# TestPowerMergeSys.net
KiCad netlist of a schematic drawn in Altium Designer
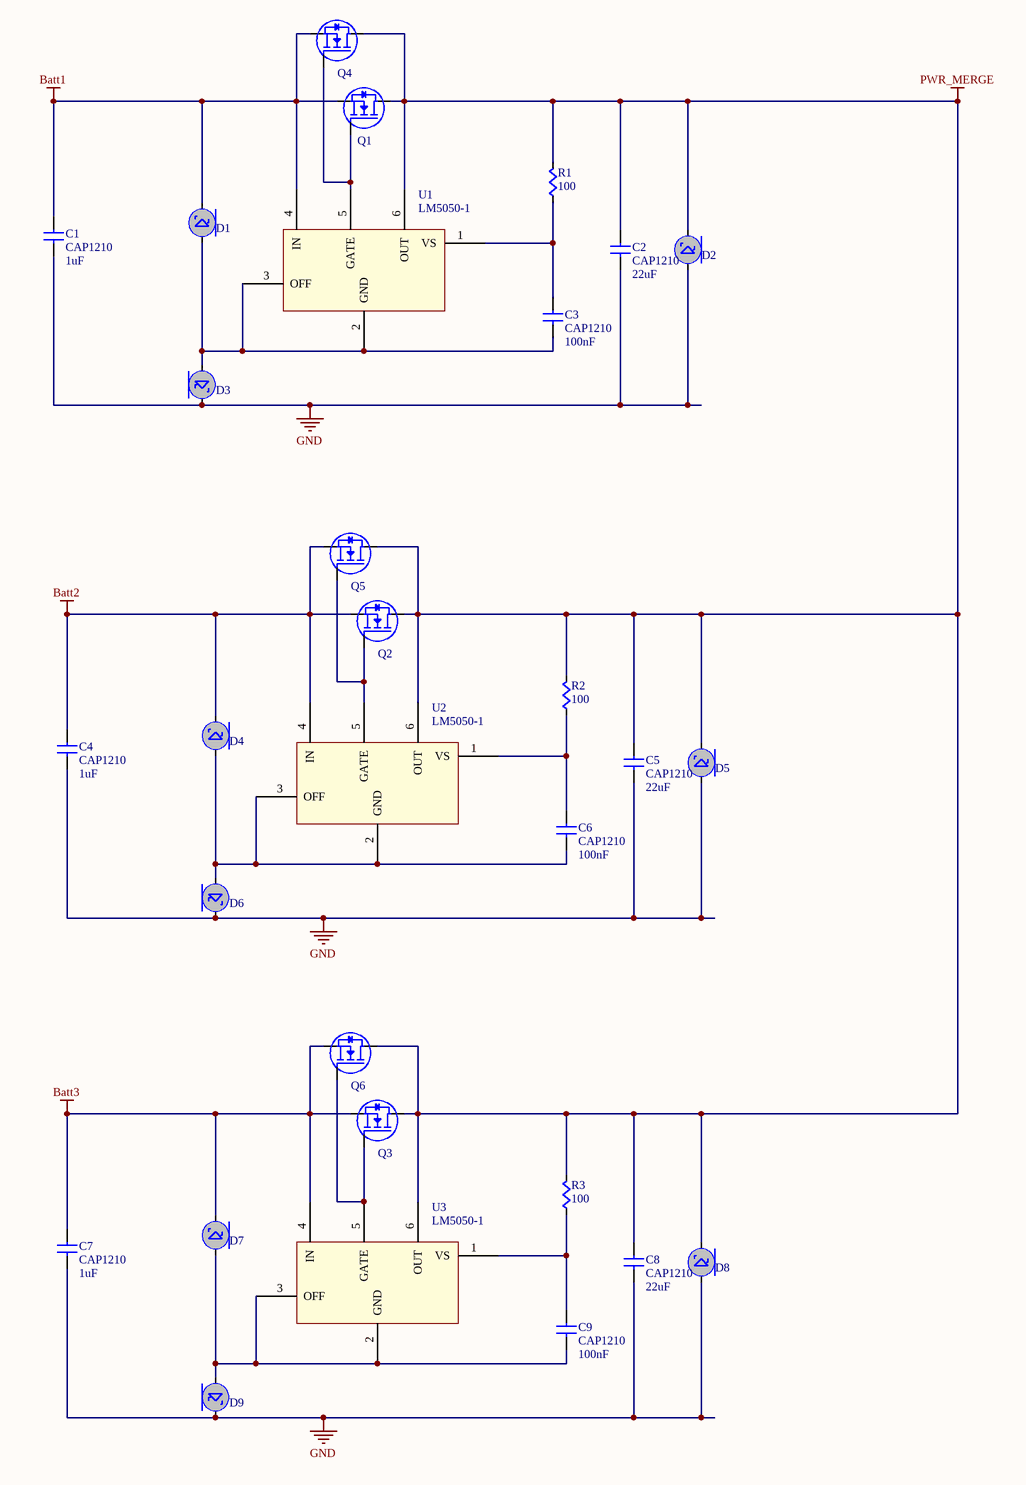
[diagram p0: TestPowerMergeSys.SchDoc]

(export (version "E")
  (design (tool "Eeschema 10.0.6"))
  (components
    (comp (ref "C1")
      (value "CAP1210")
      (footprint "CAP1210")
      (description "CAP CER 10UF 50V 20% X5R 1210")
      (fields (field (name "ALTIUM_VALUE") "1uF"))
      (libsource (lib "SubjuGator8") (part "CAP1210"))
    )
    (comp (ref "C2")
      (value "CAP1210")
      (footprint "CAP1210")
      (description "CAP CER 10UF 50V 20% X5R 1210")
      (fields (field (name "ALTIUM_VALUE") "22uF"))
      (libsource (lib "SubjuGator8") (part "CAP1210"))
    )
    (comp (ref "C3")
      (value "CAP1210")
      (footprint "CAP1210")
      (description "CAP CER 10UF 50V 20% X5R 1210")
      (fields (field (name "ALTIUM_VALUE") "100nF"))
      (libsource (lib "SubjuGator8") (part "CAP1210"))
    )
    (comp (ref "C4")
      (value "CAP1210")
      (footprint "CAP1210")
      (description "CAP CER 10UF 50V 20% X5R 1210")
      (fields (field (name "ALTIUM_VALUE") "1uF"))
      (libsource (lib "SubjuGator8") (part "CAP1210"))
    )
    (comp (ref "C5")
      (value "CAP1210")
      (footprint "CAP1210")
      (description "CAP CER 10UF 50V 20% X5R 1210")
      (fields (field (name "ALTIUM_VALUE") "22uF"))
      (libsource (lib "SubjuGator8") (part "CAP1210"))
    )
    (comp (ref "C6")
      (value "CAP1210")
      (footprint "CAP1210")
      (description "CAP CER 10UF 50V 20% X5R 1210")
      (fields (field (name "ALTIUM_VALUE") "100nF"))
      (libsource (lib "SubjuGator8") (part "CAP1210"))
    )
    (comp (ref "C7")
      (value "CAP1210")
      (footprint "CAP1210")
      (description "CAP CER 10UF 50V 20% X5R 1210")
      (fields (field (name "ALTIUM_VALUE") "1uF"))
      (libsource (lib "SubjuGator8") (part "CAP1210"))
    )
    (comp (ref "C8")
      (value "CAP1210")
      (footprint "CAP1210")
      (description "CAP CER 10UF 50V 20% X5R 1210")
      (fields (field (name "ALTIUM_VALUE") "22uF"))
      (libsource (lib "SubjuGator8") (part "CAP1210"))
    )
    (comp (ref "C9")
      (value "CAP1210")
      (footprint "CAP1210")
      (description "CAP CER 10UF 50V 20% X5R 1210")
      (fields (field (name "ALTIUM_VALUE") "100nF"))
      (libsource (lib "SubjuGator8") (part "CAP1210"))
    )
    (comp (ref "D1")
      (value "SS16T3G")
      (footprint "SS16T3G")
      (description "DIODE SCHOTTKY 60V 1A SMA")
      (libsource (lib "") (part "SS16T3G_1"))
    )
    (comp (ref "D2")
      (value "SMBJ60A-13-F")
      (footprint "SMBJ60A-13-F")
      (description "TVS UNIDIRECT 600W 60V SMB")
      (libsource (lib "SubjuGator8") (part "SMBJ60A-13-F"))
    )
    (comp (ref "D3")
      (value "SS16T3G")
      (footprint "SS16T3G")
      (description "DIODE SCHOTTKY 60V 1A SMA")
      (libsource (lib "SubjuGator8") (part "SS16T3G"))
    )
    (comp (ref "D4")
      (value "SS16T3G")
      (footprint "SS16T3G")
      (description "DIODE SCHOTTKY 60V 1A SMA")
      (libsource (lib "") (part "SS16T3G_1"))
    )
    (comp (ref "D5")
      (value "SMBJ60A-13-F")
      (footprint "SMBJ60A-13-F")
      (description "TVS UNIDIRECT 600W 60V SMB")
      (libsource (lib "SubjuGator8") (part "SMBJ60A-13-F"))
    )
    (comp (ref "D6")
      (value "SS16T3G")
      (footprint "SS16T3G")
      (description "DIODE SCHOTTKY 60V 1A SMA")
      (libsource (lib "SubjuGator8") (part "SS16T3G"))
    )
    (comp (ref "D7")
      (value "SS16T3G")
      (footprint "SS16T3G")
      (description "DIODE SCHOTTKY 60V 1A SMA")
      (libsource (lib "") (part "SS16T3G_1"))
    )
    (comp (ref "D8")
      (value "SMBJ60A-13-F")
      (footprint "SMBJ60A-13-F")
      (description "TVS UNIDIRECT 600W 60V SMB")
      (libsource (lib "SubjuGator8") (part "SMBJ60A-13-F"))
    )
    (comp (ref "D9")
      (value "SS16T3G")
      (footprint "SS16T3G")
      (description "DIODE SCHOTTKY 60V 1A SMA")
      (libsource (lib "SubjuGator8") (part "SS16T3G"))
    )
    (comp (ref "Q1")
      (value "IRFB3306PbF")
      (footprint "TO-220AB Heatsink")
      (description "HEXFET Power MOSFET")
      (libsource (lib "SubjuGator8") (part "IRFx3306PbF"))
    )
    (comp (ref "Q2")
      (value "IRFB3306PbF")
      (footprint "TO-220AB Heatsink")
      (description "HEXFET Power MOSFET")
      (libsource (lib "SubjuGator8") (part "IRFx3306PbF"))
    )
    (comp (ref "Q3")
      (value "IRFB3306PbF")
      (footprint "TO-220AB Heatsink")
      (description "HEXFET Power MOSFET")
      (libsource (lib "SubjuGator8") (part "IRFx3306PbF"))
    )
    (comp (ref "Q4")
      (value "IRFB3306PbF")
      (footprint "TO-220AB Heatsink")
      (description "HEXFET Power MOSFET")
      (libsource (lib "SubjuGator8") (part "IRFx3306PbF"))
    )
    (comp (ref "Q5")
      (value "IRFB3306PbF")
      (footprint "TO-220AB Heatsink")
      (description "HEXFET Power MOSFET")
      (libsource (lib "SubjuGator8") (part "IRFx3306PbF"))
    )
    (comp (ref "Q6")
      (value "IRFB3306PbF")
      (footprint "TO-220AB Heatsink")
      (description "HEXFET Power MOSFET")
      (libsource (lib "SubjuGator8") (part "IRFx3306PbF"))
    )
    (comp (ref "R1")
      (value "100")
      (footprint "RES0603")
      (fields (field (name "Comment") "Res"))
      (libsource (lib "SubjuGator8") (part "Res"))
    )
    (comp (ref "R2")
      (value "100")
      (footprint "RES0603")
      (fields (field (name "Comment") "Res"))
      (libsource (lib "SubjuGator8") (part "Res"))
    )
    (comp (ref "R3")
      (value "100")
      (footprint "RES0603")
      (fields (field (name "Comment") "Res"))
      (libsource (lib "SubjuGator8") (part "Res"))
    )
    (comp (ref "U1")
      (value "LM5050-1")
      (footprint "LM5050")
      (description "High-Side OR-ing FET Controller")
      (libsource (lib "SubjuGator8") (part "LM5050"))
    )
    (comp (ref "U2")
      (value "LM5050-1")
      (footprint "LM5050")
      (description "High-Side OR-ing FET Controller")
      (libsource (lib "SubjuGator8") (part "LM5050"))
    )
    (comp (ref "U3")
      (value "LM5050-1")
      (footprint "LM5050")
      (description "High-Side OR-ing FET Controller")
      (libsource (lib "SubjuGator8") (part "LM5050"))
    )
  )
  (nets
    (net (code "1") (name "Batt1") (class "Default")
      (node (ref "C1") (pin "1") (pinfunction "A_1") (pintype "passive"))
      (node (ref "D1") (pin "C") (pinfunction "C_C") (pintype "passive"))
      (node (ref "Q1") (pin "S") (pinfunction "S_S") (pintype "passive"))
      (node (ref "Q4") (pin "S") (pinfunction "S_S") (pintype "passive"))
      (node (ref "U1") (pin "4") (pinfunction "IN_4") (pintype "passive"))
    )
    (net (code "2") (name "Batt2") (class "Default")
      (node (ref "C4") (pin "1") (pinfunction "A_1") (pintype "passive"))
      (node (ref "D4") (pin "C") (pinfunction "C_C") (pintype "passive"))
      (node (ref "Q2") (pin "S") (pinfunction "S_S") (pintype "passive"))
      (node (ref "Q5") (pin "S") (pinfunction "S_S") (pintype "passive"))
      (node (ref "U2") (pin "4") (pinfunction "IN_4") (pintype "passive"))
    )
    (net (code "3") (name "Batt3") (class "Default")
      (node (ref "C7") (pin "1") (pinfunction "A_1") (pintype "passive"))
      (node (ref "D7") (pin "C") (pinfunction "C_C") (pintype "passive"))
      (node (ref "Q3") (pin "S") (pinfunction "S_S") (pintype "passive"))
      (node (ref "Q6") (pin "S") (pinfunction "S_S") (pintype "passive"))
      (node (ref "U3") (pin "4") (pinfunction "IN_4") (pintype "passive"))
    )
    (net (code "4") (name "GND") (class "Default")
      (node (ref "C1") (pin "2") (pinfunction "B_2") (pintype "passive"))
      (node (ref "C2") (pin "2") (pinfunction "B_2") (pintype "passive"))
      (node (ref "C4") (pin "2") (pinfunction "B_2") (pintype "passive"))
      (node (ref "C5") (pin "2") (pinfunction "B_2") (pintype "passive"))
      (node (ref "C7") (pin "2") (pinfunction "B_2") (pintype "passive"))
      (node (ref "C8") (pin "2") (pinfunction "B_2") (pintype "passive"))
      (node (ref "D2") (pin "A") (pinfunction "A_A") (pintype "passive"))
      (node (ref "D3") (pin "C") (pinfunction "C_C") (pintype "passive"))
      (node (ref "D5") (pin "A") (pinfunction "A_A") (pintype "passive"))
      (node (ref "D6") (pin "C") (pinfunction "C_C") (pintype "passive"))
      (node (ref "D8") (pin "A") (pinfunction "A_A") (pintype "passive"))
      (node (ref "D9") (pin "C") (pinfunction "C_C") (pintype "passive"))
    )
    (net (code "5") (name "Net-(C3-A)") (class "Default")
      (node (ref "C3") (pin "1") (pinfunction "A_1") (pintype "passive"))
      (node (ref "R1") (pin "2") (pinfunction "B_2") (pintype "passive"))
      (node (ref "U1") (pin "1") (pinfunction "VS_1") (pintype "passive"))
    )
    (net (code "6") (name "Net-(C3-B)") (class "Default")
      (node (ref "C3") (pin "2") (pinfunction "B_2") (pintype "passive"))
      (node (ref "D1") (pin "A") (pinfunction "A_A") (pintype "passive"))
      (node (ref "D3") (pin "A") (pinfunction "A_A") (pintype "passive"))
      (node (ref "U1") (pin "2") (pinfunction "GND_2") (pintype "passive"))
      (node (ref "U1") (pin "3") (pinfunction "OFF_3") (pintype "passive"))
    )
    (net (code "7") (name "Net-(C6-A)") (class "Default")
      (node (ref "C6") (pin "1") (pinfunction "A_1") (pintype "passive"))
      (node (ref "R2") (pin "2") (pinfunction "B_2") (pintype "passive"))
      (node (ref "U2") (pin "1") (pinfunction "VS_1") (pintype "passive"))
    )
    (net (code "8") (name "Net-(C6-B)") (class "Default")
      (node (ref "C6") (pin "2") (pinfunction "B_2") (pintype "passive"))
      (node (ref "D4") (pin "A") (pinfunction "A_A") (pintype "passive"))
      (node (ref "D6") (pin "A") (pinfunction "A_A") (pintype "passive"))
      (node (ref "U2") (pin "2") (pinfunction "GND_2") (pintype "passive"))
      (node (ref "U2") (pin "3") (pinfunction "OFF_3") (pintype "passive"))
    )
    (net (code "9") (name "Net-(C9-A)") (class "Default")
      (node (ref "C9") (pin "1") (pinfunction "A_1") (pintype "passive"))
      (node (ref "R3") (pin "2") (pinfunction "B_2") (pintype "passive"))
      (node (ref "U3") (pin "1") (pinfunction "VS_1") (pintype "passive"))
    )
    (net (code "10") (name "Net-(C9-B)") (class "Default")
      (node (ref "C9") (pin "2") (pinfunction "B_2") (pintype "passive"))
      (node (ref "D7") (pin "A") (pinfunction "A_A") (pintype "passive"))
      (node (ref "D9") (pin "A") (pinfunction "A_A") (pintype "passive"))
      (node (ref "U3") (pin "2") (pinfunction "GND_2") (pintype "passive"))
      (node (ref "U3") (pin "3") (pinfunction "OFF_3") (pintype "passive"))
    )
    (net (code "11") (name "Net-(U1-GATE)") (class "Default")
      (node (ref "Q1") (pin "G") (pinfunction "G_G") (pintype "passive"))
      (node (ref "Q4") (pin "G") (pinfunction "G_G") (pintype "passive"))
      (node (ref "U1") (pin "5") (pinfunction "GATE_5") (pintype "passive"))
    )
    (net (code "12") (name "Net-(U2-GATE)") (class "Default")
      (node (ref "Q2") (pin "G") (pinfunction "G_G") (pintype "passive"))
      (node (ref "Q5") (pin "G") (pinfunction "G_G") (pintype "passive"))
      (node (ref "U2") (pin "5") (pinfunction "GATE_5") (pintype "passive"))
    )
    (net (code "13") (name "Net-(U3-GATE)") (class "Default")
      (node (ref "Q3") (pin "G") (pinfunction "G_G") (pintype "passive"))
      (node (ref "Q6") (pin "G") (pinfunction "G_G") (pintype "passive"))
      (node (ref "U3") (pin "5") (pinfunction "GATE_5") (pintype "passive"))
    )
    (net (code "14") (name "PWR_MERGE") (class "Default")
      (node (ref "C2") (pin "1") (pinfunction "A_1") (pintype "passive"))
      (node (ref "C5") (pin "1") (pinfunction "A_1") (pintype "passive"))
      (node (ref "C8") (pin "1") (pinfunction "A_1") (pintype "passive"))
      (node (ref "D2") (pin "C") (pinfunction "C_C") (pintype "passive"))
      (node (ref "D5") (pin "C") (pinfunction "C_C") (pintype "passive"))
      (node (ref "D8") (pin "C") (pinfunction "C_C") (pintype "passive"))
      (node (ref "Q1") (pin "D") (pinfunction "D_D") (pintype "passive"))
      (node (ref "Q2") (pin "D") (pinfunction "D_D") (pintype "passive"))
      (node (ref "Q3") (pin "D") (pinfunction "D_D") (pintype "passive"))
      (node (ref "Q4") (pin "D") (pinfunction "D_D") (pintype "passive"))
      (node (ref "Q5") (pin "D") (pinfunction "D_D") (pintype "passive"))
      (node (ref "Q6") (pin "D") (pinfunction "D_D") (pintype "passive"))
      (node (ref "R1") (pin "1") (pinfunction "A_1") (pintype "passive"))
      (node (ref "R2") (pin "1") (pinfunction "A_1") (pintype "passive"))
      (node (ref "R3") (pin "1") (pinfunction "A_1") (pintype "passive"))
      (node (ref "U1") (pin "6") (pinfunction "OUT_6") (pintype "passive"))
      (node (ref "U2") (pin "6") (pinfunction "OUT_6") (pintype "passive"))
      (node (ref "U3") (pin "6") (pinfunction "OUT_6") (pintype "passive"))
    )
  )
)
